# J-Link_to_STDC14.net
KiCad netlist of a schematic drawn in Altium Designer
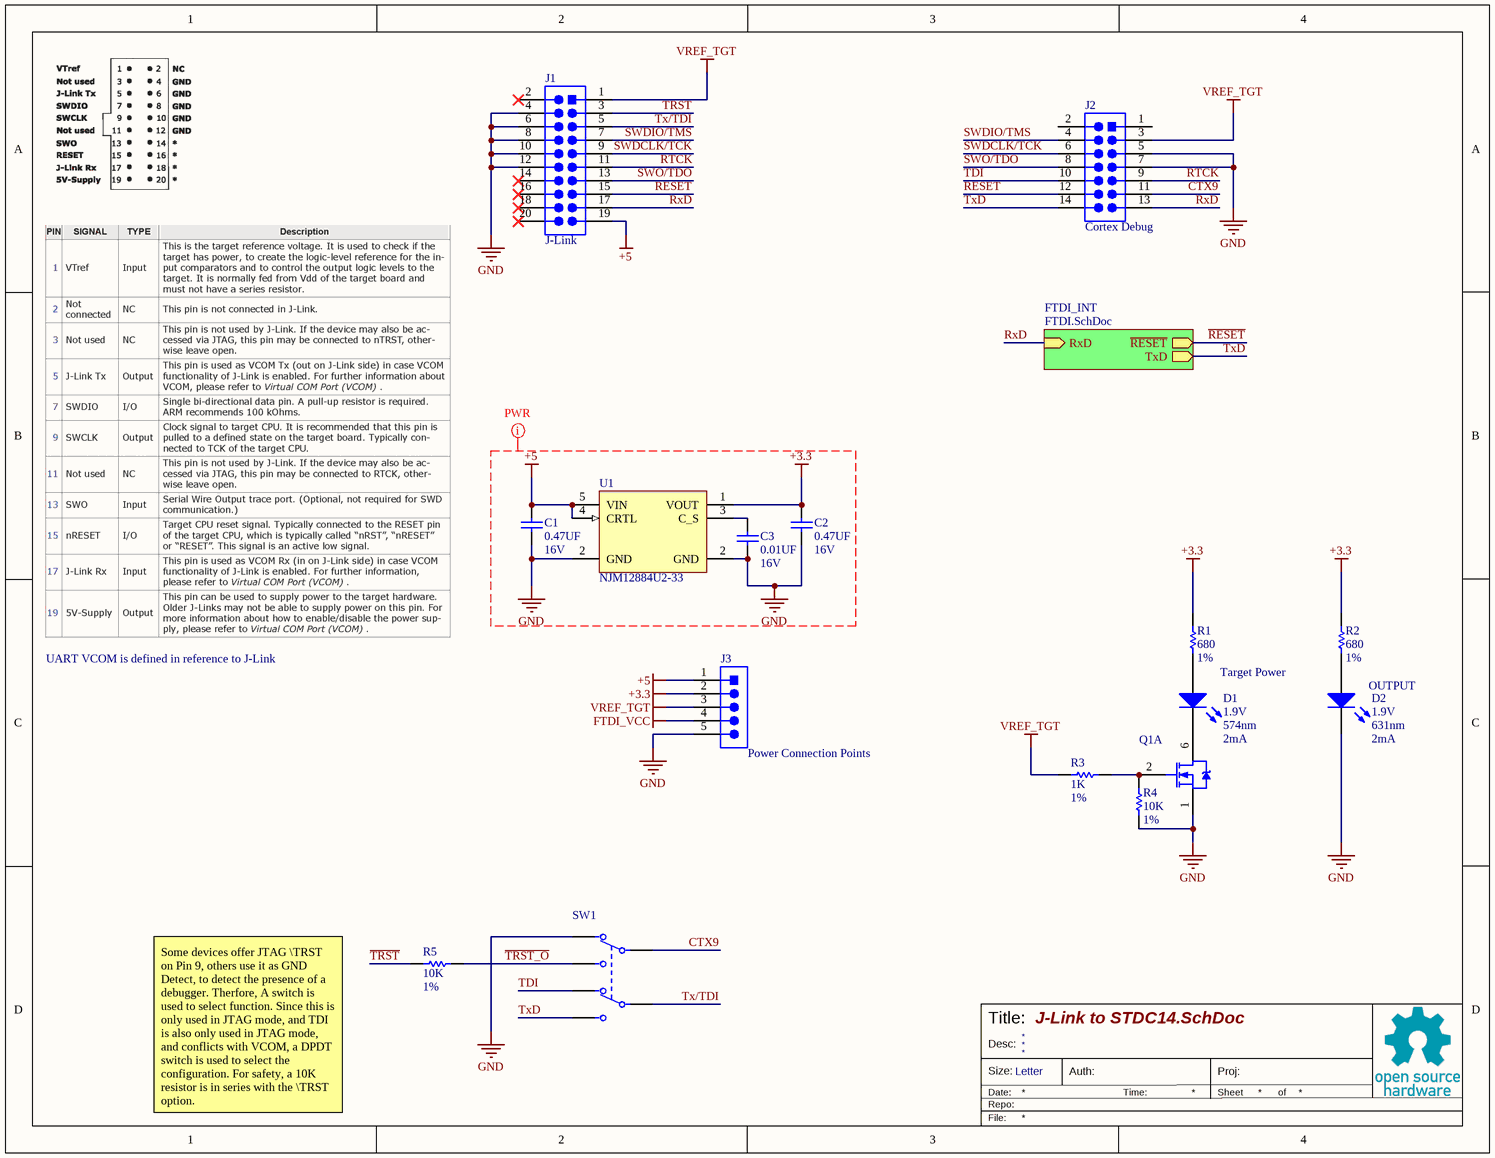
[diagram p0: J-Link to STDC14.SchDoc]

(export (version "E")
  (design (tool "Eeschema 10.0.6"))
  (components
    (comp (ref "C1")
      (value "CAP 0603 0.47UF 16V 10% X7R")
      (footprint "0603_CAP")
      (description "Capacitor Surface Mount 0603 Footprint 0.47UF 16V 10% Tolerance Ceramic X7R")
      (fields
        (field (name "VAL") "0.47UF")
        (field (name "VOL") "16V")
        (field (name "MANUFACTURER") "Various")
        (field (name "VOLTAGE") "16V")
      )
      (libsource (lib "Passive Components") (part "cap"))
    )
    (comp (ref "C2")
      (value "CAP 0603 0.47UF 16V 10% X7R")
      (footprint "0603_CAP")
      (description "Capacitor Surface Mount 0603 Footprint 0.47UF 16V 10% Tolerance Ceramic X7R")
      (fields
        (field (name "VAL") "0.47UF")
        (field (name "VOL") "16V")
        (field (name "MANUFACTURER") "Various")
        (field (name "VOLTAGE") "16V")
      )
      (libsource (lib "Passive Components") (part "cap"))
    )
    (comp (ref "C3")
      (value "CAP 0603 0.01UF 16V 10% X7R")
      (footprint "0603_CAP")
      (description "Capacitor Surface Mount 0603 Footprint 0.01UF 16V 10% Tolerance Ceramic X7R")
      (fields
        (field (name "VAL") "0.01UF")
        (field (name "VOL") "16V")
        (field (name "MANUFACTURER") "Various")
        (field (name "VOLTAGE") "16V")
      )
      (libsource (lib "Passive Components") (part "cap"))
    )
    (comp (ref "D1")
      (value "Green LED")
      (footprint "SM0805GCL")
      (description "Green 574nm LED Indication - Discrete 1.9V 0805 (2012 Metric)")
      (fields
        (field (name "MANUFACTURER") "Bivar")
        (field (name "VOLTAGE RATING") "1.9V")
        (field (name "WAVELENGTH") "574nm")
        (field (name "TEST CURRENT") "2mA")
      )
      (libsource (lib "Discrete Semiconductors") (part "LED_Single"))
    )
    (comp (ref "D2")
      (value "Red LED")
      (footprint "SM0805HCL")
      (description "Red 631nm LED Indication - Discrete 1.9V 0805 (2012 Metric)")
      (fields
        (field (name "MANUFACTURER") "Bivar")
        (field (name "VOLTAGE RATING") "1.9V")
        (field (name "WAVELENGTH") "631nm")
        (field (name "TEST CURRENT") "2mA")
      )
      (libsource (lib "Discrete Semiconductors") (part "LED_Single"))
    )
    (comp (ref "J1")
      (value "20 contact Female header, RA")
      (footprint "SFH11-PBPC-D10-RA-BK")
      (description "20 Position Header Connector  Through Hole, Right Angle")
      (fields (field (name "MANUFACTURER") "Sullins"))
      (libsource (lib "Connectors") (part "Header 10X2"))
    )
    (comp (ref "J2")
      (value "STDC14 Debug Connector")
      (footprint "FTSH-107-01-F-DV-K PLUGOUT")
      (description "STDC14 Debug Connector (ST Micro extension to the Cortex 10 Pin), 0.050\" (1.27mm) Pitch")
      (fields (field (name "MANUFACTURER") "Samtec"))
      (libsource (lib "Connectors") (part "STDC14"))
    )
    (comp (ref "J3")
      (value "5 contacts Male header")
      (footprint "70543-0109 - slim")
      (description "Connector Male Header 1X5 vertical 5contacts 0.100in pitch 0.76um Gold finish shrouded with latch")
      (fields (field (name "MANUFACTURER") "Molex"))
      (libsource (lib "Connectors") (part "Header 1X5"))
    )
    (comp (ref "Q1")
      (value "Dual N-Ch MOSFET")
      (footprint "SOT363")
      (description "Dual N-Channel Enhancement Mode FET SOT-363")
      (fields (field (name "MANUFACTURER") "Fairchild Semiconductors"))
      (libsource (lib "Discrete Semiconductors") (part "2N7002DW"))
    )
    (comp (ref "R1")
      (value "RES 0603 680 1%")
      (footprint "0603_RES")
      (description "Resistor Surface Mount, 680 Ohms, 0603 Footprint, 1% Tolerance 0.1W")
      (fields
        (field (name "VAL") "680")
        (field (name "TOL") "1%")
        (field (name "MANUFACTURER") "Various")
        (field (name "TOLERANCE") "1%")
      )
      (libsource (lib "Passive Components") (part "res"))
    )
    (comp (ref "R2")
      (value "RES 0603 680 1%")
      (footprint "0603_RES")
      (description "Resistor Surface Mount, 680 Ohms, 0603 Footprint, 1% Tolerance 0.1W")
      (fields
        (field (name "VAL") "680")
        (field (name "TOL") "1%")
        (field (name "MANUFACTURER") "Various")
        (field (name "TOLERANCE") "1%")
      )
      (libsource (lib "Passive Components") (part "res"))
    )
    (comp (ref "R3")
      (value "RES 0603 1K 1%")
      (footprint "0603_RES")
      (description "Resistor Surface Mount, 1K Ohms, 0603 Footprint, 1% Tolerance 0.1W")
      (fields
        (field (name "VAL") "1K")
        (field (name "TOL") "1%")
        (field (name "MANUFACTURER") "Various")
        (field (name "TOLERANCE") "1%")
      )
      (libsource (lib "Passive Components") (part "res"))
    )
    (comp (ref "R4")
      (value "RES 0603 10K 1%")
      (footprint "0603_RES")
      (description "Resistor Surface Mount, 10K Ohms, 0603 Footprint, 1% Tolerance 0.1W")
      (fields
        (field (name "VAL") "10K")
        (field (name "TOL") "1%")
        (field (name "MANUFACTURER") "Various")
        (field (name "TOLERANCE") "1%")
      )
      (libsource (lib "Passive Components") (part "res"))
    )
    (comp (ref "R5")
      (value "RES 0603 10K 1%")
      (footprint "0603_RES")
      (description "Resistor Surface Mount, 10K Ohms, 0603 Footprint, 1% Tolerance 0.1W")
      (fields
        (field (name "VAL") "10K")
        (field (name "TOL") "1%")
        (field (name "MANUFACTURER") "Various")
        (field (name "TOLERANCE") "1%")
      )
      (libsource (lib "Passive Components") (part "res"))
    )
    (comp (ref "SW1")
      (value "SWITCH SLIDE DPDT 300MA 6V")
      (footprint "JS202011CQN")
      (description "Slide Switch DPDT Through Hole")
      (fields (field (name "MANUFACTURER PART NUMBER") "JS202011CQN") (field (name "MANUFACTURER") "C&K"))
      (libsource (lib "Electromechanical") (part "DPDT"))
    )
    (comp (ref "U1")
      (value "3.3V LDO Soft start reverse current reverse voltage")
      (footprint "SOT89-5_NJR")
      (description "Linear Voltage Regulator IC  1 Output  500mA SOT-89-5")
      (fields (field (name "P/N") "NJM12884U2-33") (field (name "MANUFACTURER") "NJR Corporation/NJRC"))
      (libsource (lib "Integrated Circuits") (part "NJM12884U2"))
    )
  )
  (nets
    (net (code "1") (name "+3.3") (class "Default")
      (node (ref "C2") (pin "2") (pinfunction "2_2") (pintype "passive"))
      (node (ref "J3") (pin "2") (pinfunction "2_2") (pintype "passive"))
      (node (ref "R1") (pin "2") (pinfunction "2_2") (pintype "passive"))
      (node (ref "R2") (pin "2") (pinfunction "2_2") (pintype "passive"))
      (node (ref "U1") (pin "1") (pinfunction "VOUT_1") (pintype "power_in"))
    )
    (net (code "2") (name "+5") (class "Default")
      (node (ref "C1") (pin "2") (pinfunction "2_2") (pintype "passive"))
      (node (ref "J1") (pin "19") (pinfunction "19_19") (pintype "passive"))
      (node (ref "J3") (pin "1") (pinfunction "1_1") (pintype "passive"))
      (node (ref "U1") (pin "4") (pinfunction "CRTL_4") (pintype "input"))
      (node (ref "U1") (pin "5") (pinfunction "VIN_5") (pintype "power_in"))
    )
    (net (code "3") (name "/CTX9") (class "Default")
      (node (ref "J2") (pin "11") (pinfunction "GNDDetect_11") (pintype "power_in"))
      (node (ref "SW1") (pin "2") (pinfunction "2_2") (pintype "passive"))
    )
    (net (code "4") (name "/RESET") (class "Default")
      (node (ref "J1") (pin "15") (pinfunction "15_15") (pintype "passive"))
      (node (ref "J2") (pin "12") (pinfunction "RESET_12") (pintype "passive"))
    )
    (net (code "5") (name "/RTCK") (class "Default")
      (node (ref "J1") (pin "11") (pinfunction "11_11") (pintype "passive"))
      (node (ref "J2") (pin "9") (pinfunction "RCLK_9") (pintype "passive"))
    )
    (net (code "6") (name "/RxD") (class "Default")
      (node (ref "J1") (pin "17") (pinfunction "17_17") (pintype "passive"))
      (node (ref "J2") (pin "13") (pinfunction "TxD_13") (pintype "passive"))
    )
    (net (code "7") (name "/SWDCLK{slash}TCK") (class "Default")
      (node (ref "J1") (pin "9") (pinfunction "9_9") (pintype "passive"))
      (node (ref "J2") (pin "6") (pinfunction "SWDCLK/TCK/TCK_6") (pintype "passive"))
    )
    (net (code "8") (name "/SWDIO{slash}TMS") (class "Default")
      (node (ref "J1") (pin "7") (pinfunction "7_7") (pintype "passive"))
      (node (ref "J2") (pin "4") (pinfunction "SWDIO/TMS/TMS_4") (pintype "passive"))
    )
    (net (code "9") (name "/SWO{slash}TDO") (class "Default")
      (node (ref "J1") (pin "13") (pinfunction "13_13") (pintype "passive"))
      (node (ref "J2") (pin "8") (pinfunction "SWO/TDO/TDO_8") (pintype "passive"))
    )
    (net (code "10") (name "/TDI") (class "Default")
      (node (ref "J2") (pin "10") (pinfunction "NC/TDI_10") (pintype "passive"))
      (node (ref "SW1") (pin "4") (pinfunction "4_4") (pintype "passive"))
    )
    (net (code "11") (name "/TRST") (class "Default")
      (node (ref "J1") (pin "3") (pinfunction "3_3") (pintype "passive"))
      (node (ref "R5") (pin "1") (pinfunction "1_1") (pintype "passive"))
    )
    (net (code "12") (name "/TRST_O") (class "Default")
      (node (ref "R5") (pin "2") (pinfunction "2_2") (pintype "passive"))
      (node (ref "SW1") (pin "3") (pinfunction "3_3") (pintype "passive"))
    )
    (net (code "13") (name "/TxD") (class "Default")
      (node (ref "J2") (pin "14") (pinfunction "RxD_14") (pintype "passive"))
      (node (ref "SW1") (pin "6") (pinfunction "6_6") (pintype "passive"))
    )
    (net (code "14") (name "/Tx{slash}TDI") (class "Default")
      (node (ref "J1") (pin "5") (pinfunction "5_5") (pintype "passive"))
      (node (ref "SW1") (pin "5") (pinfunction "5_5") (pintype "passive"))
    )
    (net (code "15") (name "FTDI_VCC") (class "Default")
      (node (ref "J3") (pin "4") (pinfunction "4_4") (pintype "passive"))
    )
    (net (code "16") (name "GND") (class "Default")
      (node (ref "C1") (pin "1") (pinfunction "1_1") (pintype "passive"))
      (node (ref "C2") (pin "1") (pinfunction "1_1") (pintype "passive"))
      (node (ref "C3") (pin "1") (pinfunction "1_1") (pintype "passive"))
      (node (ref "D2") (pin "K") (pinfunction "K_K") (pintype "passive"))
      (node (ref "J1") (pin "10") (pinfunction "10_10") (pintype "passive"))
      (node (ref "J1") (pin "12") (pinfunction "12_12") (pintype "passive"))
      (node (ref "J1") (pin "4") (pinfunction "4_4") (pintype "passive"))
      (node (ref "J1") (pin "6") (pinfunction "6_6") (pintype "passive"))
      (node (ref "J1") (pin "8") (pinfunction "8_8") (pintype "passive"))
      (node (ref "J2") (pin "5") (pinfunction "GND_5") (pintype "power_in"))
      (node (ref "J2") (pin "7") (pinfunction "GND_7") (pintype "power_in"))
      (node (ref "J3") (pin "5") (pinfunction "5_5") (pintype "passive"))
      (node (ref "Q1") (pin "1") (pinfunction "S_1") (pintype "passive"))
      (node (ref "R4") (pin "1") (pinfunction "1_1") (pintype "passive"))
      (node (ref "SW1") (pin "1") (pinfunction "1_1") (pintype "passive"))
      (node (ref "U1") (pin "2") (pinfunction "GND_2") (pintype "power_in"))
    )
    (net (code "17") (name "Net-(D1-PadA)") (class "Default")
      (node (ref "D1") (pin "A") (pinfunction "A_A") (pintype "passive"))
      (node (ref "R1") (pin "1") (pinfunction "1_1") (pintype "passive"))
    )
    (net (code "18") (name "Net-(D2-PadA)") (class "Default")
      (node (ref "D2") (pin "A") (pinfunction "A_A") (pintype "passive"))
      (node (ref "R2") (pin "1") (pinfunction "1_1") (pintype "passive"))
    )
    (net (code "19") (name "Net-(Q1A-D)") (class "Default")
      (node (ref "D1") (pin "K") (pinfunction "K_K") (pintype "passive"))
      (node (ref "Q1") (pin "6") (pinfunction "D_6") (pintype "passive"))
    )
    (net (code "20") (name "Net-(Q1A-G)") (class "Default")
      (node (ref "Q1") (pin "2") (pinfunction "G_2") (pintype "passive"))
      (node (ref "R3") (pin "2") (pinfunction "2_2") (pintype "passive"))
      (node (ref "R4") (pin "2") (pinfunction "2_2") (pintype "passive"))
    )
    (net (code "21") (name "Net-(U1-C_S)") (class "Default")
      (node (ref "C3") (pin "2") (pinfunction "2_2") (pintype "passive"))
      (node (ref "U1") (pin "3") (pinfunction "C_S_3") (pintype "passive"))
    )
    (net (code "22") (name "VREF_TGT") (class "Default")
      (node (ref "J1") (pin "1") (pinfunction "1_1") (pintype "passive"))
      (node (ref "J2") (pin "3") (pinfunction "VCC_3") (pintype "power_in"))
      (node (ref "J3") (pin "3") (pinfunction "3_3") (pintype "passive"))
      (node (ref "R3") (pin "1") (pinfunction "1_1") (pintype "passive"))
    )
    (net (code "23") (name "unconnected-(J1-Pad2)") (class "Default")
      (node (ref "J1") (pin "2") (pinfunction "2_2") (pintype "passive+no_connect"))
    )
    (net (code "24") (name "unconnected-(J1-Pad14)") (class "Default")
      (node (ref "J1") (pin "14") (pinfunction "14_14") (pintype "passive+no_connect"))
    )
    (net (code "25") (name "unconnected-(J1-Pad16)") (class "Default")
      (node (ref "J1") (pin "16") (pinfunction "16_16") (pintype "passive+no_connect"))
    )
    (net (code "26") (name "unconnected-(J1-Pad18)") (class "Default")
      (node (ref "J1") (pin "18") (pinfunction "18_18") (pintype "passive+no_connect"))
    )
    (net (code "27") (name "unconnected-(J1-Pad20)") (class "Default")
      (node (ref "J1") (pin "20") (pinfunction "20_20") (pintype "passive+no_connect"))
    )
    (net (code "28") (name "unconnected-(J2-Reserved-Pad1)") (class "Default")
      (node (ref "J2") (pin "1") (pinfunction "Reserved_1") (pintype "passive"))
    )
    (net (code "29") (name "unconnected-(J2-Reserved-Pad2)") (class "Default")
      (node (ref "J2") (pin "2") (pinfunction "Reserved_2") (pintype "passive"))
    )
  )
)
